# feather-power-switch-mk-2_0.net
KiCad netlist of a schematic drawn in EAGLE
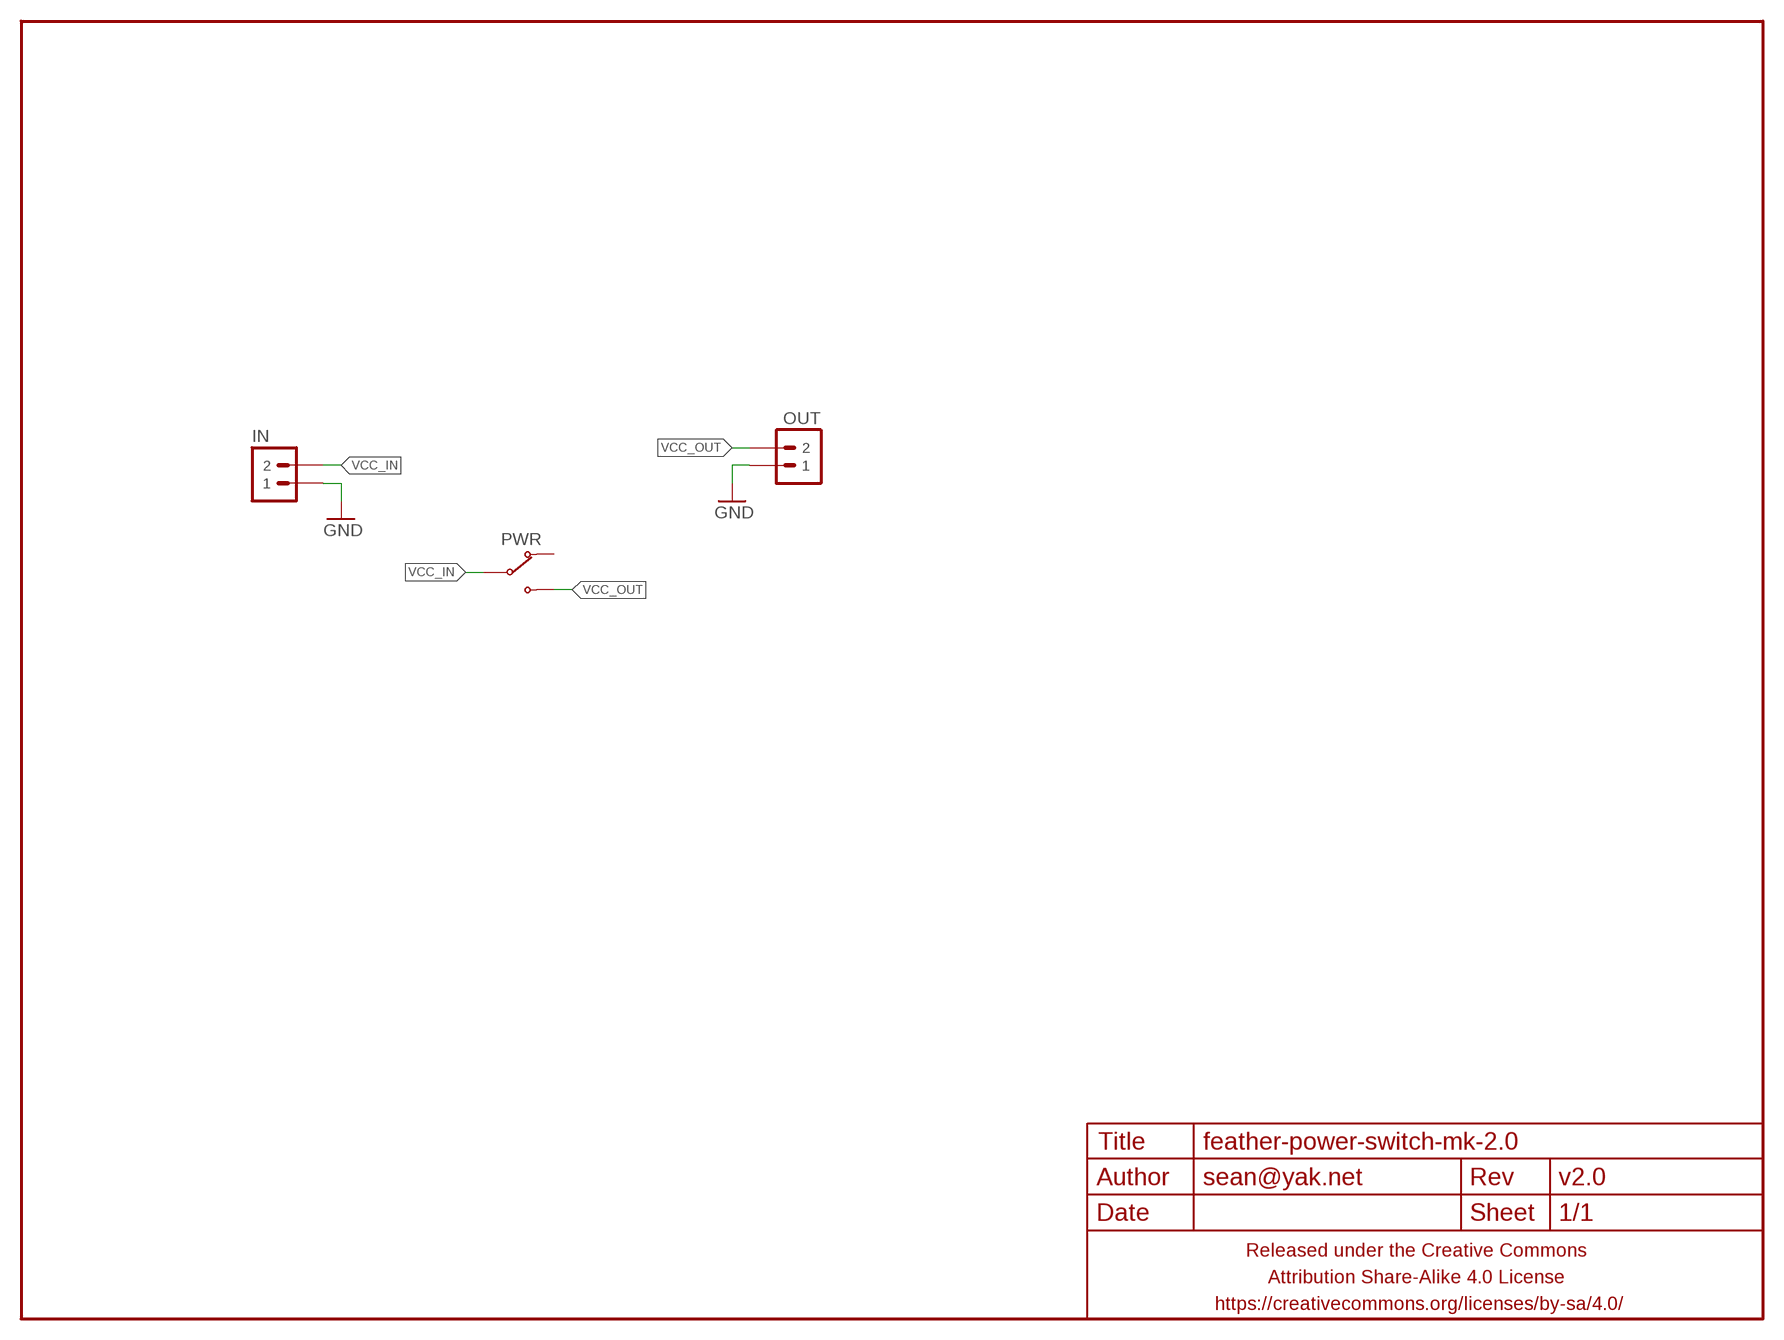
[diagram p0: schematic, sheet 1]

(export (version "E")
  (design (tool "Eeschema 10.0.6"))
  (components
    (comp (ref "FRAME1")
      (value "FRAME-LETTERNO_PACKAGE")
      (footprint "eagle-import:DUMMY")
      (fields (field (name "DESIGNER") "sean@yak.net") (field (name "VERSION") "v2.0"))
      (libsource (lib "eagle-import") (part "FRAME-LETTERNO_PACKAGE"))
    )
    (comp (ref "IN")
      (value "M02PTH-CENTERED-R+")
      (footprint "eagle-import:1X02-CENTER-R+")
      (libsource (lib "eagle-import") (part "M02PTH-CENTERED-R+"))
    )
    (comp (ref "OUT")
      (value "M02PTH-CENTERED-R+")
      (footprint "eagle-import:1X02-CENTER-R+")
      (libsource (lib "eagle-import") (part "M02PTH-CENTERED-R+"))
    )
    (comp (ref "PWR")
      (value "SWITCH-SPDTSMD-RA")
      (footprint "eagle-import:SWITCH-SPDT-SMD-RA")
      (libsource (lib "eagle-import") (part "SWITCH-SPDTSMD-RA"))
    )
  )
  (nets
    (net (code "1") (name "GND") (class "Default")
      (node (ref "IN") (pin "1") (pinfunction "1_1") (pintype "passive"))
      (node (ref "OUT") (pin "1") (pinfunction "1_1") (pintype "passive"))
    )
    (net (code "2") (name "VCC_IN") (class "Default")
      (node (ref "IN") (pin "2") (pinfunction "2_2") (pintype "passive"))
      (node (ref "PWR") (pin "2") (pinfunction "COM_2") (pintype "passive"))
    )
    (net (code "3") (name "VCC_OUT") (class "Default")
      (node (ref "OUT") (pin "2") (pinfunction "2_2") (pintype "passive"))
      (node (ref "PWR") (pin "1") (pinfunction "NO_1") (pintype "passive"))
    )
    (net (code "4") (name "unconnected-(PWR-NC-Pad3)") (class "Default")
      (node (ref "PWR") (pin "3") (pinfunction "NC_3") (pintype "passive"))
    )
  )
)
